# Rx.net
KiCad netlist of a schematic drawn in Altium Designer
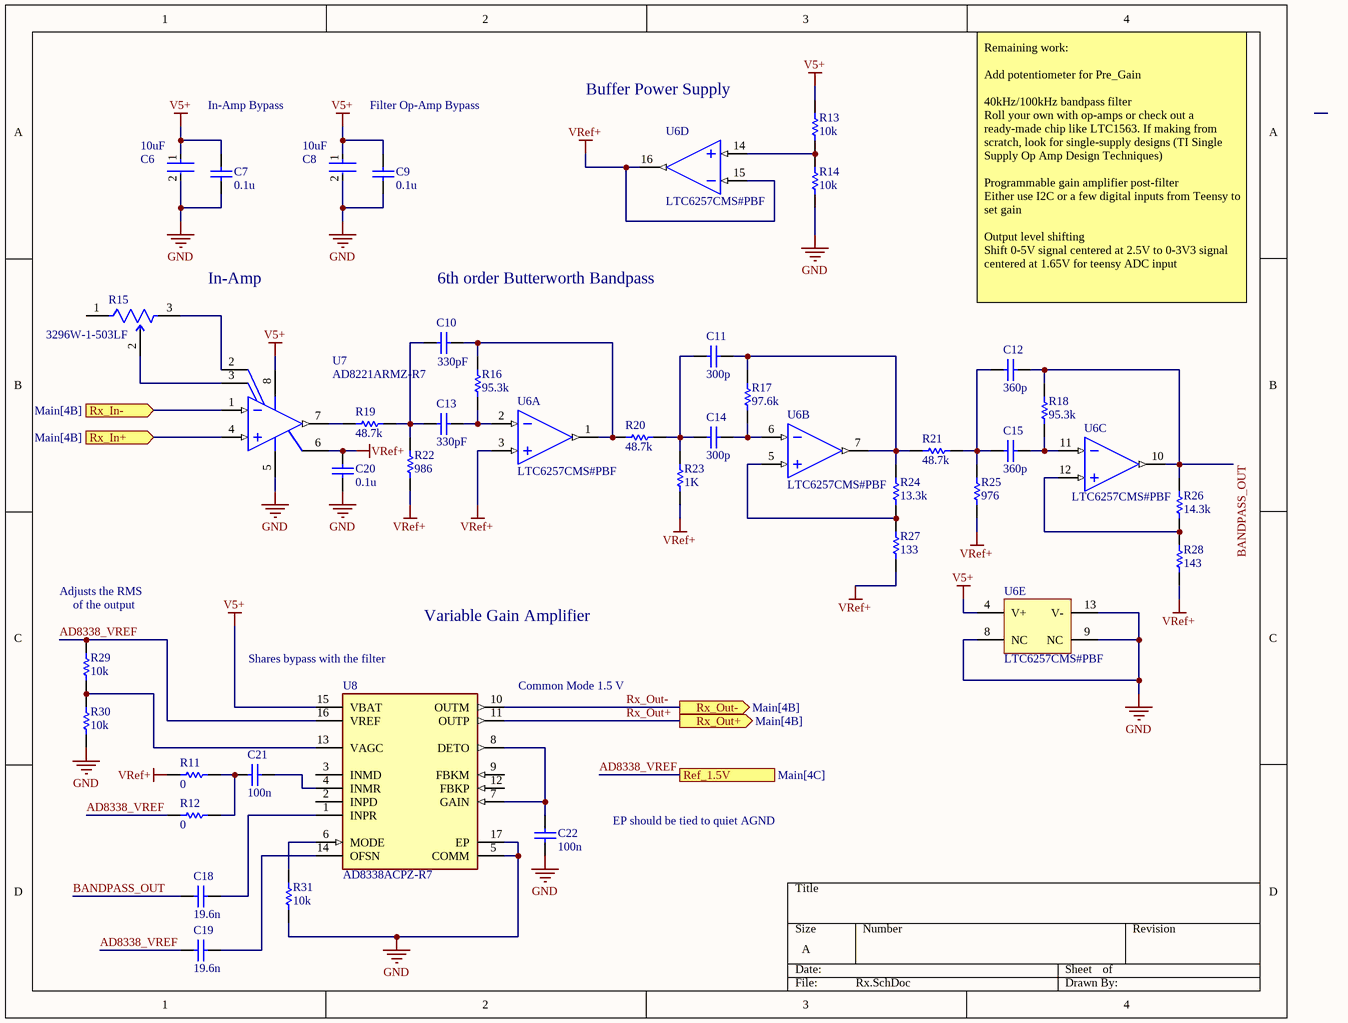
[diagram p0: Rx.SchDoc]

(export (version "E")
  (design (tool "Eeschema 10.0.6"))
  (components
    (comp (ref "C6")
      (value "C3216X5R1H106K160AB")
      (footprint "FP-C3216-160-0_2-IPC_A")
      (description "Multilayer Ceramic Capacitors 10uF ±10% 50V X5R SMD 1206")
      (fields
        (field (name "TOLERANCE") "10%")
        (field (name "VOLTAGE") "50V")
        (field (name "CAPACITANCE") "10uF")
      )
      (libsource (lib "Altium Content Vault") (part "11868f565c42a9108669ba33697ecf6"))
    )
    (comp (ref "C7")
      (value "0.1u")
      (footprint "0805")
      (description "Capacitor")
      (libsource (lib "Simulation Generic Components") (part "Capacitor"))
    )
    (comp (ref "C8")
      (value "C3216X5R1H106K160AB")
      (footprint "FP-C3216-160-0_2-IPC_A")
      (description "Multilayer Ceramic Capacitors 10uF ±10% 50V X5R SMD 1206")
      (fields
        (field (name "TOLERANCE") "10%")
        (field (name "VOLTAGE") "50V")
        (field (name "CAPACITANCE") "10uF")
      )
      (libsource (lib "Altium Content Vault") (part "11868f565c42a9108669ba33697ecf6"))
    )
    (comp (ref "C9")
      (value "0.1u")
      (footprint "0805")
      (description "Capacitor")
      (libsource (lib "Simulation Generic Components") (part "Capacitor"))
    )
    (comp (ref "C10")
      (value "330pF")
      (footprint "0805")
      (description "Capacitor")
      (libsource (lib "Simulation Generic Components") (part "Capacitor"))
    )
    (comp (ref "C11")
      (value "300p")
      (footprint "0805")
      (description "Capacitor")
      (libsource (lib "Simulation Generic Components") (part "Capacitor"))
    )
    (comp (ref "C12")
      (value "360p")
      (footprint "0805")
      (description "Capacitor")
      (libsource (lib "Simulation Generic Components") (part "Capacitor"))
    )
    (comp (ref "C13")
      (value "330pF")
      (footprint "0805")
      (description "Capacitor")
      (libsource (lib "Simulation Generic Components") (part "Capacitor"))
    )
    (comp (ref "C14")
      (value "300p")
      (footprint "0805")
      (description "Capacitor")
      (libsource (lib "Simulation Generic Components") (part "Capacitor"))
    )
    (comp (ref "C15")
      (value "360p")
      (footprint "0805")
      (description "Capacitor")
      (libsource (lib "Simulation Generic Components") (part "Capacitor"))
    )
    (comp (ref "C18")
      (value "19.6n")
      (footprint "0805")
      (description "Capacitor")
      (libsource (lib "Simulation Generic Components") (part "Capacitor"))
    )
    (comp (ref "C19")
      (value "19.6n")
      (footprint "0805")
      (description "Capacitor")
      (libsource (lib "Simulation Generic Components") (part "Capacitor"))
    )
    (comp (ref "C20")
      (value "0.1u")
      (footprint "0805")
      (description "Capacitor")
      (libsource (lib "Simulation Generic Components") (part "Capacitor"))
    )
    (comp (ref "C21")
      (value "100n")
      (footprint "0805")
      (description "Capacitor")
      (libsource (lib "Simulation Generic Components") (part "Capacitor"))
    )
    (comp (ref "C22")
      (value "100n")
      (footprint "0805")
      (description "Capacitor")
      (libsource (lib "Simulation Generic Components") (part "Capacitor"))
    )
    (comp (ref "R11")
      (value "0")
      (footprint "0805")
      (description "Resistor")
      (libsource (lib "Simulation Generic Components") (part "Resistor"))
    )
    (comp (ref "R12")
      (value "0")
      (footprint "0805")
      (description "Resistor")
      (libsource (lib "Simulation Generic Components") (part "Resistor"))
    )
    (comp (ref "R13")
      (value "10k")
      (footprint "0805")
      (description "Resistor")
      (libsource (lib "Simulation Generic Components") (part "Resistor"))
    )
    (comp (ref "R14")
      (value "10k")
      (footprint "0805")
      (description "Resistor")
      (libsource (lib "Simulation Generic Components") (part "Resistor"))
    )
    (comp (ref "R15")
      (value "3296W-1-503LF")
      (footprint "FP-3296W-MFG")
      (description "TRIMMER 50K OHM 0.5W PC PIN TOP")
      (fields (field (name "TOLERANCE") "10%"))
      (libsource (lib "Altium Content Vault") (part "2dcfd2547301a7d3209a5e99acfd772"))
    )
    (comp (ref "R16")
      (value "95.3k")
      (footprint "0805")
      (description "Resistor")
      (libsource (lib "Simulation Generic Components") (part "Resistor"))
    )
    (comp (ref "R17")
      (value "97.6k")
      (footprint "0805")
      (description "Resistor")
      (libsource (lib "Simulation Generic Components") (part "Resistor"))
    )
    (comp (ref "R18")
      (value "95.3k")
      (footprint "0805")
      (description "Resistor")
      (libsource (lib "Simulation Generic Components") (part "Resistor"))
    )
    (comp (ref "R19")
      (value "48.7k")
      (footprint "0805")
      (fields
        (field (name "MANUFACTURER") "Panasonic")
        (field (name "MANUFACTURER PART NUMBER") "ERJ-6ENF4872V")
        (field (name "TOLERANCE") "1%")
      )
      (libsource (lib "Simulation Generic Components") (part "Resistor"))
    )
    (comp (ref "R20")
      (value "48.7k")
      (footprint "0805")
      (fields
        (field (name "MANUFACTURER") "Panasonic")
        (field (name "MANUFACTURER PART NUMBER") "ERJ-6ENF4872V")
        (field (name "TOLERANCE") "1%")
      )
      (libsource (lib "Simulation Generic Components") (part "Resistor"))
    )
    (comp (ref "R21")
      (value "48.7k")
      (footprint "0805")
      (description "Resistor")
      (libsource (lib "Simulation Generic Components") (part "Resistor"))
    )
    (comp (ref "R22")
      (value "986")
      (footprint "0805")
      (description "Resistor")
      (libsource (lib "Simulation Generic Components") (part "Resistor"))
    )
    (comp (ref "R23")
      (value "1K")
      (footprint "0805")
      (description "Resistor")
      (libsource (lib "Simulation Generic Components") (part "Resistor"))
    )
    (comp (ref "R24")
      (value "13.3k")
      (footprint "0805")
      (description "Resistor")
      (libsource (lib "Simulation Generic Components") (part "Resistor"))
    )
    (comp (ref "R25")
      (value "976")
      (footprint "0805")
      (description "Resistor")
      (libsource (lib "Simulation Generic Components") (part "Resistor"))
    )
    (comp (ref "R26")
      (value "14.3k")
      (footprint "0805")
      (description "Resistor")
      (libsource (lib "Simulation Generic Components") (part "Resistor"))
    )
    (comp (ref "R27")
      (value "133")
      (footprint "0805")
      (description "Resistor")
      (libsource (lib "Simulation Generic Components") (part "Resistor"))
    )
    (comp (ref "R28")
      (value "143")
      (footprint "0805")
      (description "Resistor")
      (libsource (lib "Simulation Generic Components") (part "Resistor"))
    )
    (comp (ref "R29")
      (value "10k")
      (footprint "0805")
      (description "Resistor")
      (libsource (lib "Simulation Generic Components") (part "Resistor"))
    )
    (comp (ref "R30")
      (value "10k")
      (footprint "0805")
      (description "Resistor")
      (libsource (lib "Simulation Generic Components") (part "Resistor"))
    )
    (comp (ref "R31")
      (value "10k")
      (footprint "0805")
      (description "Resistor")
      (libsource (lib "Simulation Generic Components") (part "Resistor"))
    )
    (comp (ref "U6")
      (value "LTC6257CMS#PBF")
      (footprint "LT-MS-16_N")
      (fields
        (field (name "MANUFACTURER") "Linear Technology")
        (field (name "LINEAR TECHNOLOGY PART NUMBER") "LTC6257")
        (field (name "MANUFACTURER PART NUMBER") "ERJ-6ENF4872V")
      )
      (libsource (lib "Altium Content Vault") (part "LT-LTC608X-LTC607X-16"))
    )
    (comp (ref "U7")
      (value "AD8221ARMZ-R7")
      (footprint "ADI-RM-8_L")
      (fields (field (name "MANUFACTURER") "Analog Devices"))
      (libsource (lib "Altium Content Vault") (part "ADI-AD8221-8"))
    )
    (comp (ref "U8")
      (value "AD8338ACPZ-R7")
      (footprint "FP-CP-16-22-IPC_C")
      (description "IC OPAMP VGA 1 CIRCUIT 16LFCSP")
      (fields
        (field (name "OCTOPART") "https://octopart.com/ad8338acpz-r7-analog+devices-21054770")
        (field (name "MANUFACTURER") "Analog Devices")
      )
      (libsource (lib "Altium Content Vault") (part "4ce7887af0b7713ffabab50ab6d8fb3"))
    )
  )
  (nets
    (net (code "1") (name "/AD8338_VREF") (class "Default")
      (node (ref "C19") (pin "2") (pinfunction "2_2") (pintype "passive"))
      (node (ref "R12") (pin "2") (pinfunction "2_2") (pintype "passive"))
      (node (ref "R29") (pin "2") (pinfunction "2_2") (pintype "passive"))
      (node (ref "U8") (pin "16") (pinfunction "VREF_16") (pintype "power_in"))
    )
    (net (code "2") (name "/BANDPASS_OUT") (class "Default")
      (node (ref "C12") (pin "1") (pinfunction "1_1") (pintype "passive"))
      (node (ref "C18") (pin "2") (pinfunction "2_2") (pintype "passive"))
      (node (ref "R18") (pin "2") (pinfunction "2_2") (pintype "passive"))
      (node (ref "R26") (pin "2") (pinfunction "2_2") (pintype "passive"))
      (node (ref "U6") (pin "10") (pinfunction "OUT_C_10") (pintype "output"))
    )
    (net (code "3") (name "/Rx_In+") (class "Default")
      (node (ref "U7") (pin "4") (pinfunction "IN+_4") (pintype "input"))
    )
    (net (code "4") (name "/Rx_In-") (class "Default")
      (node (ref "U7") (pin "1") (pinfunction "IN-_1") (pintype "input"))
    )
    (net (code "5") (name "/Rx_Out+") (class "Default")
      (node (ref "U8") (pin "11") (pinfunction "OUTP_11") (pintype "output"))
    )
    (net (code "6") (name "/Rx_Out-") (class "Default")
      (node (ref "U8") (pin "10") (pinfunction "OUTM_10") (pintype "output"))
    )
    (net (code "7") (name "GND") (class "Default")
      (node (ref "C20") (pin "1") (pinfunction "1_1") (pintype "passive"))
      (node (ref "C22") (pin "1") (pinfunction "1_1") (pintype "passive"))
      (node (ref "C6") (pin "2") (pinfunction "2_2") (pintype "passive"))
      (node (ref "C7") (pin "1") (pinfunction "1_1") (pintype "passive"))
      (node (ref "C8") (pin "2") (pinfunction "2_2") (pintype "passive"))
      (node (ref "C9") (pin "1") (pinfunction "1_1") (pintype "passive"))
      (node (ref "R14") (pin "1") (pinfunction "1_1") (pintype "passive"))
      (node (ref "R30") (pin "1") (pinfunction "1_1") (pintype "passive"))
      (node (ref "R31") (pin "1") (pinfunction "1_1") (pintype "passive"))
      (node (ref "U6") (pin "13") (pinfunction "V-_13") (pintype "power_in"))
      (node (ref "U6") (pin "8") (pinfunction "NC_8") (pintype "passive"))
      (node (ref "U6") (pin "9") (pinfunction "NC_9") (pintype "passive"))
      (node (ref "U7") (pin "5") (pinfunction "VS-_5") (pintype "power_in"))
      (node (ref "U8") (pin "17") (pinfunction "EP_17") (pintype "power_in"))
      (node (ref "U8") (pin "5") (pinfunction "COMM_5") (pintype "power_in"))
    )
    (net (code "8") (name "Net-(C10-Pad2)") (class "Default")
      (node (ref "C10") (pin "2") (pinfunction "2_2") (pintype "passive"))
      (node (ref "C13") (pin "2") (pinfunction "2_2") (pintype "passive"))
      (node (ref "R19") (pin "2") (pinfunction "2_2") (pintype "passive"))
      (node (ref "R22") (pin "2") (pinfunction "2_2") (pintype "passive"))
    )
    (net (code "9") (name "Net-(C11-Pad2)") (class "Default")
      (node (ref "C11") (pin "2") (pinfunction "2_2") (pintype "passive"))
      (node (ref "C14") (pin "2") (pinfunction "2_2") (pintype "passive"))
      (node (ref "R20") (pin "2") (pinfunction "2_2") (pintype "passive"))
      (node (ref "R23") (pin "2") (pinfunction "2_2") (pintype "passive"))
    )
    (net (code "10") (name "Net-(C12-Pad2)") (class "Default")
      (node (ref "C12") (pin "2") (pinfunction "2_2") (pintype "passive"))
      (node (ref "C15") (pin "2") (pinfunction "2_2") (pintype "passive"))
      (node (ref "R21") (pin "2") (pinfunction "2_2") (pintype "passive"))
      (node (ref "R25") (pin "2") (pinfunction "2_2") (pintype "passive"))
    )
    (net (code "11") (name "Net-(C21-Pad2)") (class "Default")
      (node (ref "C21") (pin "2") (pinfunction "2_2") (pintype "passive"))
      (node (ref "R11") (pin "1") (pinfunction "1_1") (pintype "passive"))
      (node (ref "R12") (pin "1") (pinfunction "1_1") (pintype "passive"))
    )
    (net (code "12") (name "Net-(R15-CW)") (class "Default")
      (node (ref "R15") (pin "3") (pinfunction "CW_3") (pintype "passive"))
      (node (ref "U7") (pin "2") (pinfunction "RG_2") (pintype "passive"))
    )
    (net (code "13") (name "Net-(R15-WIPER)") (class "Default")
      (node (ref "R15") (pin "2") (pinfunction "WIPER_2") (pintype "passive"))
      (node (ref "U7") (pin "3") (pinfunction "RG_3") (pintype "passive"))
    )
    (net (code "14") (name "Net-(U6A-IN-_A)") (class "Default")
      (node (ref "C13") (pin "1") (pinfunction "1_1") (pintype "passive"))
      (node (ref "R16") (pin "1") (pinfunction "1_1") (pintype "passive"))
      (node (ref "U6") (pin "2") (pinfunction "IN-_A_2") (pintype "input"))
    )
    (net (code "15") (name "Net-(U6A-OUT_A)") (class "Default")
      (node (ref "C10") (pin "1") (pinfunction "1_1") (pintype "passive"))
      (node (ref "R16") (pin "2") (pinfunction "2_2") (pintype "passive"))
      (node (ref "R20") (pin "1") (pinfunction "1_1") (pintype "passive"))
      (node (ref "U6") (pin "1") (pinfunction "OUT_A_1") (pintype "output"))
    )
    (net (code "16") (name "Net-(U6B-IN+_B)") (class "Default")
      (node (ref "R24") (pin "1") (pinfunction "1_1") (pintype "passive"))
      (node (ref "R27") (pin "2") (pinfunction "2_2") (pintype "passive"))
      (node (ref "U6") (pin "5") (pinfunction "IN+_B_5") (pintype "input"))
    )
    (net (code "17") (name "Net-(U6B-IN-_B)") (class "Default")
      (node (ref "C14") (pin "1") (pinfunction "1_1") (pintype "passive"))
      (node (ref "R17") (pin "1") (pinfunction "1_1") (pintype "passive"))
      (node (ref "U6") (pin "6") (pinfunction "IN-_B_6") (pintype "input"))
    )
    (net (code "18") (name "Net-(U6B-OUT_B)") (class "Default")
      (node (ref "C11") (pin "1") (pinfunction "1_1") (pintype "passive"))
      (node (ref "R17") (pin "2") (pinfunction "2_2") (pintype "passive"))
      (node (ref "R21") (pin "1") (pinfunction "1_1") (pintype "passive"))
      (node (ref "R24") (pin "2") (pinfunction "2_2") (pintype "passive"))
      (node (ref "U6") (pin "7") (pinfunction "OUT_B_7") (pintype "output"))
    )
    (net (code "19") (name "Net-(U6C-IN+_C)") (class "Default")
      (node (ref "R26") (pin "1") (pinfunction "1_1") (pintype "passive"))
      (node (ref "R28") (pin "2") (pinfunction "2_2") (pintype "passive"))
      (node (ref "U6") (pin "12") (pinfunction "IN+_C_12") (pintype "input"))
    )
    (net (code "20") (name "Net-(U6C-IN-_C)") (class "Default")
      (node (ref "C15") (pin "1") (pinfunction "1_1") (pintype "passive"))
      (node (ref "R18") (pin "1") (pinfunction "1_1") (pintype "passive"))
      (node (ref "U6") (pin "11") (pinfunction "IN-_C_11") (pintype "input"))
    )
    (net (code "21") (name "Net-(U6D-IN+_D)") (class "Default")
      (node (ref "R13") (pin "1") (pinfunction "1_1") (pintype "passive"))
      (node (ref "R14") (pin "2") (pinfunction "2_2") (pintype "passive"))
      (node (ref "U6") (pin "14") (pinfunction "IN+_D_14") (pintype "input"))
    )
    (net (code "22") (name "Net-(U7-VOUT)") (class "Default")
      (node (ref "R19") (pin "1") (pinfunction "1_1") (pintype "passive"))
      (node (ref "U7") (pin "7") (pinfunction "VOUT_7") (pintype "output"))
    )
    (net (code "23") (name "Net-(U8-DETO)") (class "Default")
      (node (ref "C22") (pin "2") (pinfunction "2_2") (pintype "passive"))
      (node (ref "U8") (pin "7") (pinfunction "GAIN_7") (pintype "input"))
      (node (ref "U8") (pin "8") (pinfunction "DETO_8") (pintype "output"))
    )
    (net (code "24") (name "Net-(U8-INMR)") (class "Default")
      (node (ref "C21") (pin "1") (pinfunction "1_1") (pintype "passive"))
      (node (ref "U8") (pin "4") (pinfunction "INMR_4") (pintype "passive"))
    )
    (net (code "25") (name "Net-(U8-INPR)") (class "Default")
      (node (ref "C18") (pin "1") (pinfunction "1_1") (pintype "passive"))
      (node (ref "U8") (pin "1") (pinfunction "INPR_1") (pintype "passive"))
    )
    (net (code "26") (name "Net-(U8-MODE)") (class "Default")
      (node (ref "R31") (pin "2") (pinfunction "2_2") (pintype "passive"))
      (node (ref "U8") (pin "6") (pinfunction "MODE_6") (pintype "input"))
    )
    (net (code "27") (name "Net-(U8-OFSN)") (class "Default")
      (node (ref "C19") (pin "1") (pinfunction "1_1") (pintype "passive"))
      (node (ref "U8") (pin "14") (pinfunction "OFSN_14") (pintype "passive"))
    )
    (net (code "28") (name "Net-(U8-VAGC)") (class "Default")
      (node (ref "R29") (pin "1") (pinfunction "1_1") (pintype "passive"))
      (node (ref "R30") (pin "2") (pinfunction "2_2") (pintype "passive"))
      (node (ref "U8") (pin "13") (pinfunction "VAGC_13") (pintype "power_in"))
    )
    (net (code "29") (name "V5+") (class "Default")
      (node (ref "C6") (pin "1") (pinfunction "1_1") (pintype "passive"))
      (node (ref "C7") (pin "2") (pinfunction "2_2") (pintype "passive"))
      (node (ref "C8") (pin "1") (pinfunction "1_1") (pintype "passive"))
      (node (ref "C9") (pin "2") (pinfunction "2_2") (pintype "passive"))
      (node (ref "R13") (pin "2") (pinfunction "2_2") (pintype "passive"))
      (node (ref "U6") (pin "4") (pinfunction "V+_4") (pintype "power_in"))
      (node (ref "U7") (pin "8") (pinfunction "VS+_8") (pintype "power_in"))
      (node (ref "U8") (pin "15") (pinfunction "VBAT_15") (pintype "power_in"))
    )
    (net (code "30") (name "VRef+") (class "Default")
      (node (ref "C20") (pin "2") (pinfunction "2_2") (pintype "passive"))
      (node (ref "R11") (pin "2") (pinfunction "2_2") (pintype "passive"))
      (node (ref "R22") (pin "1") (pinfunction "1_1") (pintype "passive"))
      (node (ref "R23") (pin "1") (pinfunction "1_1") (pintype "passive"))
      (node (ref "R25") (pin "1") (pinfunction "1_1") (pintype "passive"))
      (node (ref "R27") (pin "1") (pinfunction "1_1") (pintype "passive"))
      (node (ref "R28") (pin "1") (pinfunction "1_1") (pintype "passive"))
      (node (ref "U6") (pin "15") (pinfunction "IN-_D_15") (pintype "input"))
      (node (ref "U6") (pin "16") (pinfunction "OUT_D_16") (pintype "output"))
      (node (ref "U6") (pin "3") (pinfunction "IN+_A_3") (pintype "input"))
      (node (ref "U7") (pin "6") (pinfunction "REF_6") (pintype "passive"))
    )
    (net (code "31") (name "unconnected-(R15-CCW-Pad1)") (class "Default")
      (node (ref "R15") (pin "1") (pinfunction "CCW_1") (pintype "passive"))
    )
    (net (code "32") (name "unconnected-(U8-FBKM-Pad9)") (class "Default")
      (node (ref "U8") (pin "9") (pinfunction "FBKM_9") (pintype "input"))
    )
    (net (code "33") (name "unconnected-(U8-FBKP-Pad12)") (class "Default")
      (node (ref "U8") (pin "12") (pinfunction "FBKP_12") (pintype "input"))
    )
    (net (code "34") (name "unconnected-(U8-INMD-Pad3)") (class "Default")
      (node (ref "U8") (pin "3") (pinfunction "INMD_3") (pintype "passive"))
    )
    (net (code "35") (name "unconnected-(U8-INPD-Pad2)") (class "Default")
      (node (ref "U8") (pin "2") (pinfunction "INPD_2") (pintype "passive"))
    )
  )
)
